# untitled.net
KiCad netlist of a schematic drawn in EAGLE
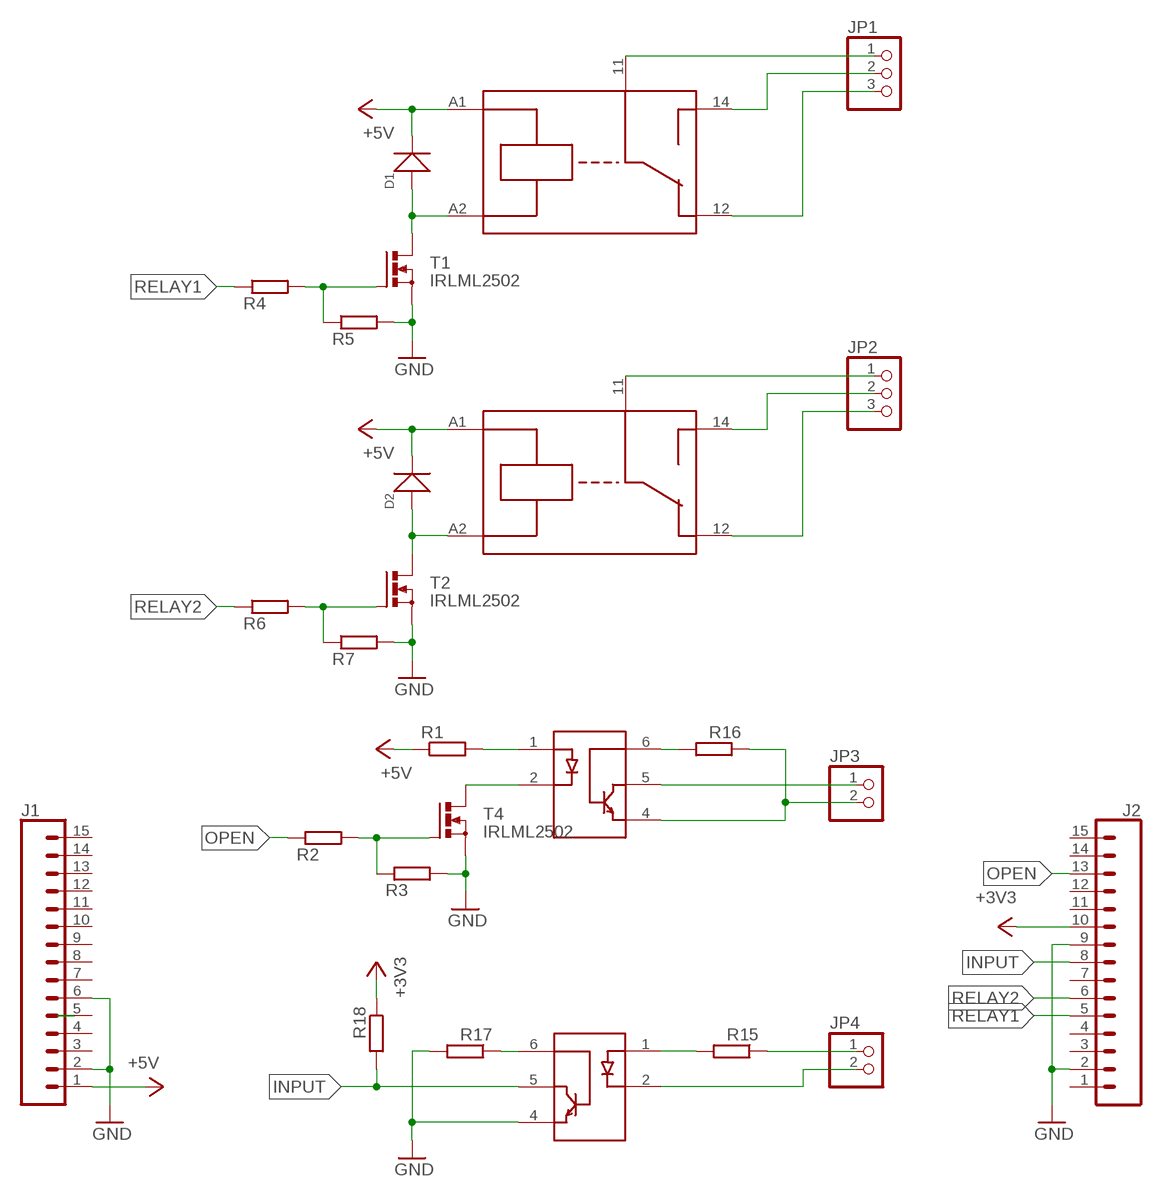
[diagram p0: schematic, sheet 1]

(export (version "E")
  (design (tool "Eeschema 10.0.6"))
  (components
    (comp (ref "D1")
      (value "1N4007")
      (footprint "eagle-import:DO-214AC")
      (libsource (lib "eagle-import") (part "DIODE-GEN-PURPOSE-1KV-1A(DO-214AC)"))
    )
    (comp (ref "D2")
      (value "1N4007")
      (footprint "eagle-import:DO-214AC")
      (libsource (lib "eagle-import") (part "DIODE-GEN-PURPOSE-1KV-1A(DO-214AC)"))
    )
    (comp (ref "J1")
      (value "CONN_15")
      (footprint "eagle-import:1X15")
      (libsource (lib "eagle-import") (part "CONN_15"))
    )
    (comp (ref "J2")
      (value "CONN_15")
      (footprint "eagle-import:1X15")
      (libsource (lib "eagle-import") (part "CONN_15"))
    )
    (comp (ref "JP1")
      (value "PINHD-1X3")
      (footprint "eagle-import:1X03")
      (libsource (lib "eagle-import") (part "PINHD-1X3"))
    )
    (comp (ref "JP2")
      (value "PINHD-1X3")
      (footprint "eagle-import:1X03")
      (libsource (lib "eagle-import") (part "PINHD-1X3"))
    )
    (comp (ref "JP3")
      (value "PINHD-1X2")
      (footprint "eagle-import:1X02")
      (libsource (lib "eagle-import") (part "PINHD-1X2"))
    )
    (comp (ref "JP4")
      (value "PINHD-1X2")
      (footprint "eagle-import:1X02")
      (libsource (lib "eagle-import") (part "PINHD-1X2"))
    )
    (comp (ref "R1")
      (value "R-EU_R0805")
      (footprint "eagle-import:R0805")
      (libsource (lib "eagle-import") (part "R-EU_R0805"))
    )
    (comp (ref "R2")
      (value "R-EU_R0805")
      (footprint "eagle-import:R0805")
      (libsource (lib "eagle-import") (part "R-EU_R0805"))
    )
    (comp (ref "R3")
      (value "R-EU_R0805")
      (footprint "eagle-import:R0805")
      (libsource (lib "eagle-import") (part "R-EU_R0805"))
    )
    (comp (ref "R4")
      (value "R-EU_R0805")
      (footprint "eagle-import:R0805")
      (libsource (lib "eagle-import") (part "R-EU_R0805"))
    )
    (comp (ref "R5")
      (value "R-EU_R0805")
      (footprint "eagle-import:R0805")
      (libsource (lib "eagle-import") (part "R-EU_R0805"))
    )
    (comp (ref "R6")
      (value "R-EU_R0805")
      (footprint "eagle-import:R0805")
      (libsource (lib "eagle-import") (part "R-EU_R0805"))
    )
    (comp (ref "R7")
      (value "R-EU_R0805")
      (footprint "eagle-import:R0805")
      (libsource (lib "eagle-import") (part "R-EU_R0805"))
    )
    (comp (ref "R15")
      (value "R-EU_R0805")
      (footprint "eagle-import:R0805")
      (libsource (lib "eagle-import") (part "R-EU_R0805"))
    )
    (comp (ref "R16")
      (value "R-EU_R0805")
      (footprint "eagle-import:R0805")
      (libsource (lib "eagle-import") (part "R-EU_R0805"))
    )
    (comp (ref "R17")
      (value "R-EU_R0805")
      (footprint "eagle-import:R0805")
      (libsource (lib "eagle-import") (part "R-EU_R0805"))
    )
    (comp (ref "R18")
      (value "R-EU_R0805")
      (footprint "eagle-import:R0805")
      (libsource (lib "eagle-import") (part "R-EU_R0805"))
    )
    (comp (ref "T1")
      (value "IRLML2502")
      (footprint "eagle-import:SOT23")
      (libsource (lib "eagle-import") (part "IRLML2502"))
    )
    (comp (ref "T2")
      (value "IRLML2502")
      (footprint "eagle-import:SOT23")
      (libsource (lib "eagle-import") (part "IRLML2502"))
    )
    (comp (ref "T4")
      (value "IRLML2502")
      (footprint "eagle-import:SOT23")
      (libsource (lib "eagle-import") (part "IRLML2502"))
    )
    (comp (ref "U$5")
      (value "PE0140")
      (footprint "eagle-import:PE0140")
      (libsource (lib "eagle-import") (part "PE0140"))
    )
    (comp (ref "U$6")
      (value "PE0140")
      (footprint "eagle-import:PE0140")
      (libsource (lib "eagle-import") (part "PE0140"))
    )
    (comp (ref "U$7")
      (value "4N35")
      (footprint "eagle-import:DIL06-SMD")
      (libsource (lib "eagle-import") (part "4N35"))
    )
    (comp (ref "U$8")
      (value "4N35")
      (footprint "eagle-import:DIL06-SMD")
      (libsource (lib "eagle-import") (part "4N35"))
    )
  )
  (nets
    (net (code "1") (name "+3V3") (class "Default")
      (node (ref "J2") (pin "10") (pinfunction "10_10") (pintype "passive"))
      (node (ref "R18") (pin "1") (pinfunction "1_1") (pintype "passive"))
    )
    (net (code "2") (name "+5V") (class "Default")
      (node (ref "D1") (pin "2") (pinfunction "-_2") (pintype "passive"))
      (node (ref "D2") (pin "2") (pinfunction "-_2") (pintype "passive"))
      (node (ref "J1") (pin "1") (pinfunction "1_1") (pintype "passive"))
      (node (ref "R1") (pin "1") (pinfunction "1_1") (pintype "passive"))
      (node (ref "U$5") (pin "A1") (pinfunction "A1_A1") (pintype "bidirectional"))
      (node (ref "U$6") (pin "A1") (pinfunction "A1_A1") (pintype "bidirectional"))
    )
    (net (code "3") (name "GND") (class "Default")
      (node (ref "J1") (pin "2") (pinfunction "2_2") (pintype "passive"))
      (node (ref "J1") (pin "6") (pinfunction "6_6") (pintype "passive"))
      (node (ref "J2") (pin "2") (pinfunction "2_2") (pintype "passive"))
      (node (ref "J2") (pin "9") (pinfunction "9_9") (pintype "passive"))
      (node (ref "R17") (pin "2") (pinfunction "2_2") (pintype "passive"))
      (node (ref "R3") (pin "2") (pinfunction "2_2") (pintype "passive"))
      (node (ref "R5") (pin "2") (pinfunction "2_2") (pintype "passive"))
      (node (ref "R7") (pin "2") (pinfunction "2_2") (pintype "passive"))
      (node (ref "T1") (pin "2") (pinfunction "S_2") (pintype "passive"))
      (node (ref "T2") (pin "2") (pinfunction "S_2") (pintype "passive"))
      (node (ref "T4") (pin "2") (pinfunction "S_2") (pintype "passive"))
      (node (ref "U$8") (pin "4") (pinfunction "E_4") (pintype "bidirectional"))
    )
    (net (code "4") (name "INPUT") (class "Default")
      (node (ref "J2") (pin "8") (pinfunction "8_8") (pintype "passive"))
      (node (ref "R18") (pin "2") (pinfunction "2_2") (pintype "passive"))
      (node (ref "U$8") (pin "5") (pinfunction "COL_5") (pintype "bidirectional"))
    )
    (net (code "5") (name "Net-(D1-+)") (class "Default")
      (node (ref "D1") (pin "1") (pinfunction "+_1") (pintype "passive"))
      (node (ref "T1") (pin "3") (pinfunction "D_3") (pintype "passive"))
      (node (ref "U$5") (pin "A2") (pinfunction "A2_A2") (pintype "bidirectional"))
    )
    (net (code "6") (name "Net-(D2-+)") (class "Default")
      (node (ref "D2") (pin "1") (pinfunction "+_1") (pintype "passive"))
      (node (ref "T2") (pin "3") (pinfunction "D_3") (pintype "passive"))
      (node (ref "U$6") (pin "A2") (pinfunction "A2_A2") (pintype "bidirectional"))
    )
    (net (code "7") (name "Net-(JP1-Pad1)") (class "Default")
      (node (ref "JP1") (pin "1") (pinfunction "1_1") (pintype "passive"))
      (node (ref "U$5") (pin "11") (pinfunction "11_11") (pintype "bidirectional"))
    )
    (net (code "8") (name "Net-(JP1-Pad2)") (class "Default")
      (node (ref "JP1") (pin "2") (pinfunction "2_2") (pintype "passive"))
      (node (ref "U$5") (pin "14") (pinfunction "14_14") (pintype "bidirectional"))
    )
    (net (code "9") (name "Net-(JP1-Pad3)") (class "Default")
      (node (ref "JP1") (pin "3") (pinfunction "3_3") (pintype "passive"))
      (node (ref "U$5") (pin "12") (pinfunction "12_12") (pintype "bidirectional"))
    )
    (net (code "10") (name "Net-(JP2-Pad1)") (class "Default")
      (node (ref "JP2") (pin "1") (pinfunction "1_1") (pintype "passive"))
      (node (ref "U$6") (pin "11") (pinfunction "11_11") (pintype "bidirectional"))
    )
    (net (code "11") (name "Net-(JP2-Pad2)") (class "Default")
      (node (ref "JP2") (pin "2") (pinfunction "2_2") (pintype "passive"))
      (node (ref "U$6") (pin "14") (pinfunction "14_14") (pintype "bidirectional"))
    )
    (net (code "12") (name "Net-(JP2-Pad3)") (class "Default")
      (node (ref "JP2") (pin "3") (pinfunction "3_3") (pintype "passive"))
      (node (ref "U$6") (pin "12") (pinfunction "12_12") (pintype "bidirectional"))
    )
    (net (code "13") (name "Net-(JP4-Pad1)") (class "Default")
      (node (ref "JP4") (pin "1") (pinfunction "1_1") (pintype "passive"))
      (node (ref "R15") (pin "1") (pinfunction "1_1") (pintype "passive"))
    )
    (net (code "14") (name "Net-(T1-G)") (class "Default")
      (node (ref "R4") (pin "2") (pinfunction "2_2") (pintype "passive"))
      (node (ref "R5") (pin "1") (pinfunction "1_1") (pintype "passive"))
      (node (ref "T1") (pin "1") (pinfunction "G_1") (pintype "passive"))
    )
    (net (code "15") (name "Net-(T2-G)") (class "Default")
      (node (ref "R6") (pin "2") (pinfunction "2_2") (pintype "passive"))
      (node (ref "R7") (pin "1") (pinfunction "1_1") (pintype "passive"))
      (node (ref "T2") (pin "1") (pinfunction "G_1") (pintype "passive"))
    )
    (net (code "16") (name "Net-(T4-D)") (class "Default")
      (node (ref "T4") (pin "3") (pinfunction "D_3") (pintype "passive"))
      (node (ref "U$7") (pin "2") (pinfunction "CAT_2") (pintype "bidirectional"))
    )
    (net (code "17") (name "Net-(T4-G)") (class "Default")
      (node (ref "R2") (pin "2") (pinfunction "2_2") (pintype "passive"))
      (node (ref "R3") (pin "1") (pinfunction "1_1") (pintype "passive"))
      (node (ref "T4") (pin "1") (pinfunction "G_1") (pintype "passive"))
    )
    (net (code "18") (name "Net-(U$7-A)") (class "Default")
      (node (ref "R1") (pin "2") (pinfunction "2_2") (pintype "passive"))
      (node (ref "U$7") (pin "1") (pinfunction "A_1") (pintype "bidirectional"))
    )
    (net (code "19") (name "Net-(U$7-B)") (class "Default")
      (node (ref "R16") (pin "2") (pinfunction "2_2") (pintype "passive"))
      (node (ref "U$7") (pin "6") (pinfunction "B_6") (pintype "bidirectional"))
    )
    (net (code "20") (name "Net-(U$7-COL)") (class "Default")
      (node (ref "JP3") (pin "1") (pinfunction "1_1") (pintype "passive"))
      (node (ref "U$7") (pin "5") (pinfunction "COL_5") (pintype "bidirectional"))
    )
    (net (code "21") (name "Net-(U$7-E)") (class "Default")
      (node (ref "JP3") (pin "2") (pinfunction "2_2") (pintype "passive"))
      (node (ref "R16") (pin "1") (pinfunction "1_1") (pintype "passive"))
      (node (ref "U$7") (pin "4") (pinfunction "E_4") (pintype "bidirectional"))
    )
    (net (code "22") (name "Net-(U$8-A)") (class "Default")
      (node (ref "R15") (pin "2") (pinfunction "2_2") (pintype "passive"))
      (node (ref "U$8") (pin "1") (pinfunction "A_1") (pintype "bidirectional"))
    )
    (net (code "23") (name "Net-(U$8-B)") (class "Default")
      (node (ref "R17") (pin "1") (pinfunction "1_1") (pintype "passive"))
      (node (ref "U$8") (pin "6") (pinfunction "B_6") (pintype "bidirectional"))
    )
    (net (code "24") (name "Net-(U$8-CAT)") (class "Default")
      (node (ref "JP4") (pin "2") (pinfunction "2_2") (pintype "passive"))
      (node (ref "U$8") (pin "2") (pinfunction "CAT_2") (pintype "bidirectional"))
    )
    (net (code "25") (name "OPEN") (class "Default")
      (node (ref "J2") (pin "13") (pinfunction "13_13") (pintype "passive"))
      (node (ref "R2") (pin "1") (pinfunction "1_1") (pintype "passive"))
    )
    (net (code "26") (name "RELAY1") (class "Default")
      (node (ref "J2") (pin "5") (pinfunction "5_5") (pintype "passive"))
      (node (ref "R4") (pin "1") (pinfunction "1_1") (pintype "passive"))
    )
    (net (code "27") (name "RELAY2") (class "Default")
      (node (ref "J2") (pin "6") (pinfunction "6_6") (pintype "passive"))
      (node (ref "R6") (pin "1") (pinfunction "1_1") (pintype "passive"))
    )
    (net (code "28") (name "unconnected-(J1-Pad3)") (class "Default")
      (node (ref "J1") (pin "3") (pinfunction "3_3") (pintype "passive"))
    )
    (net (code "29") (name "unconnected-(J1-Pad4)") (class "Default")
      (node (ref "J1") (pin "4") (pinfunction "4_4") (pintype "passive"))
    )
    (net (code "30") (name "unconnected-(J1-Pad5)") (class "Default")
      (node (ref "J1") (pin "5") (pinfunction "5_5") (pintype "passive"))
    )
    (net (code "31") (name "unconnected-(J1-Pad7)") (class "Default")
      (node (ref "J1") (pin "7") (pinfunction "7_7") (pintype "passive"))
    )
    (net (code "32") (name "unconnected-(J1-Pad8)") (class "Default")
      (node (ref "J1") (pin "8") (pinfunction "8_8") (pintype "passive"))
    )
    (net (code "33") (name "unconnected-(J1-Pad9)") (class "Default")
      (node (ref "J1") (pin "9") (pinfunction "9_9") (pintype "passive"))
    )
    (net (code "34") (name "unconnected-(J1-Pad10)") (class "Default")
      (node (ref "J1") (pin "10") (pinfunction "10_10") (pintype "passive"))
    )
    (net (code "35") (name "unconnected-(J1-Pad11)") (class "Default")
      (node (ref "J1") (pin "11") (pinfunction "11_11") (pintype "passive"))
    )
    (net (code "36") (name "unconnected-(J1-Pad12)") (class "Default")
      (node (ref "J1") (pin "12") (pinfunction "12_12") (pintype "passive"))
    )
    (net (code "37") (name "unconnected-(J1-Pad13)") (class "Default")
      (node (ref "J1") (pin "13") (pinfunction "13_13") (pintype "passive"))
    )
    (net (code "38") (name "unconnected-(J1-Pad14)") (class "Default")
      (node (ref "J1") (pin "14") (pinfunction "14_14") (pintype "passive"))
    )
    (net (code "39") (name "unconnected-(J1-Pad15)") (class "Default")
      (node (ref "J1") (pin "15") (pinfunction "15_15") (pintype "passive"))
    )
    (net (code "40") (name "unconnected-(J2-Pad1)") (class "Default")
      (node (ref "J2") (pin "1") (pinfunction "1_1") (pintype "passive"))
    )
    (net (code "41") (name "unconnected-(J2-Pad3)") (class "Default")
      (node (ref "J2") (pin "3") (pinfunction "3_3") (pintype "passive"))
    )
    (net (code "42") (name "unconnected-(J2-Pad4)") (class "Default")
      (node (ref "J2") (pin "4") (pinfunction "4_4") (pintype "passive"))
    )
    (net (code "43") (name "unconnected-(J2-Pad7)") (class "Default")
      (node (ref "J2") (pin "7") (pinfunction "7_7") (pintype "passive"))
    )
    (net (code "44") (name "unconnected-(J2-Pad11)") (class "Default")
      (node (ref "J2") (pin "11") (pinfunction "11_11") (pintype "passive"))
    )
    (net (code "45") (name "unconnected-(J2-Pad12)") (class "Default")
      (node (ref "J2") (pin "12") (pinfunction "12_12") (pintype "passive"))
    )
    (net (code "46") (name "unconnected-(J2-Pad14)") (class "Default")
      (node (ref "J2") (pin "14") (pinfunction "14_14") (pintype "passive"))
    )
    (net (code "47") (name "unconnected-(J2-Pad15)") (class "Default")
      (node (ref "J2") (pin "15") (pinfunction "15_15") (pintype "passive"))
    )
  )
)
